# Charge_Board.net
KiCad netlist of a schematic drawn in EAGLE
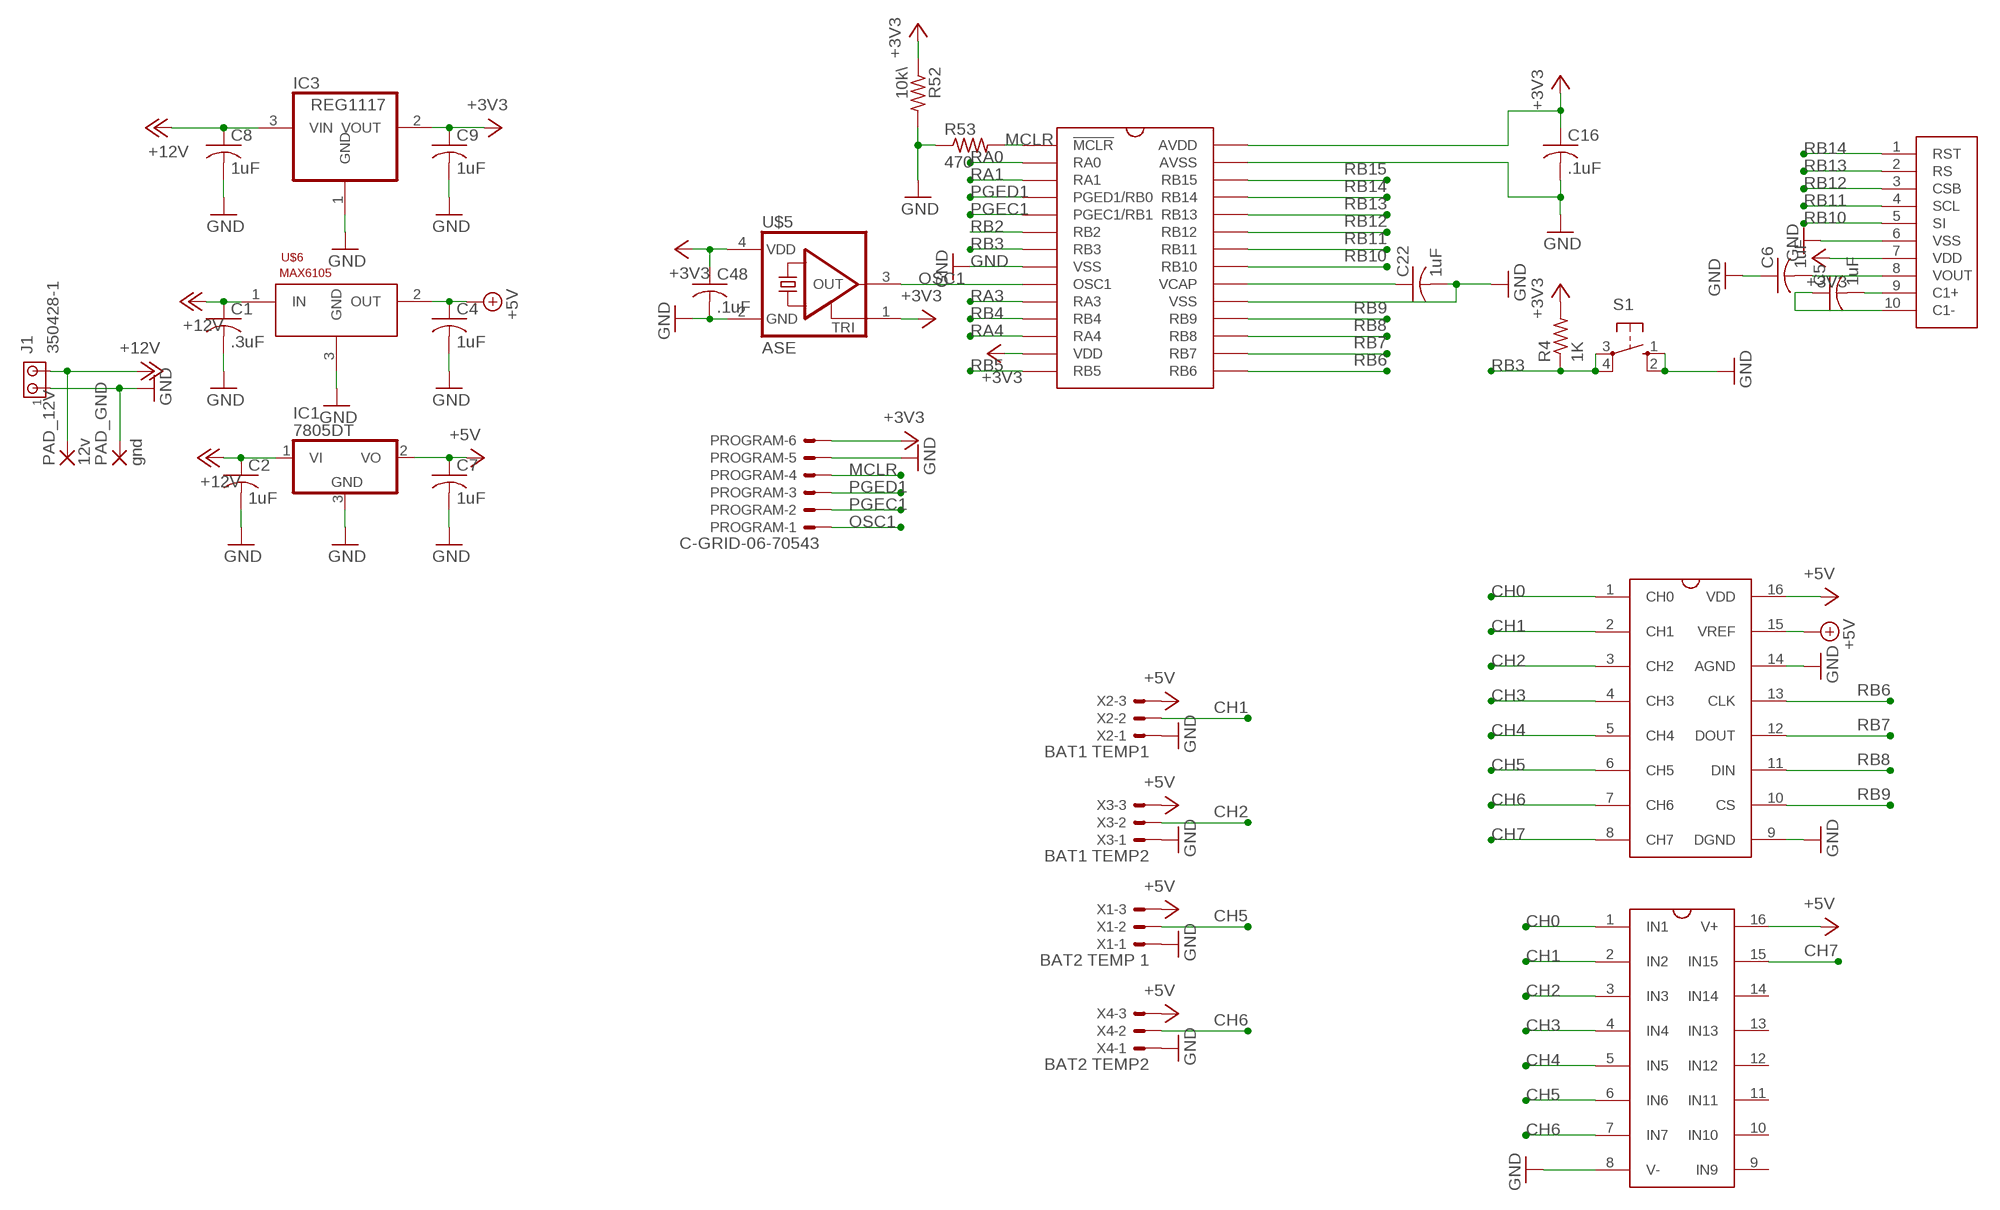
[diagram p0: schematic, sheet 1, part 1 of 2]
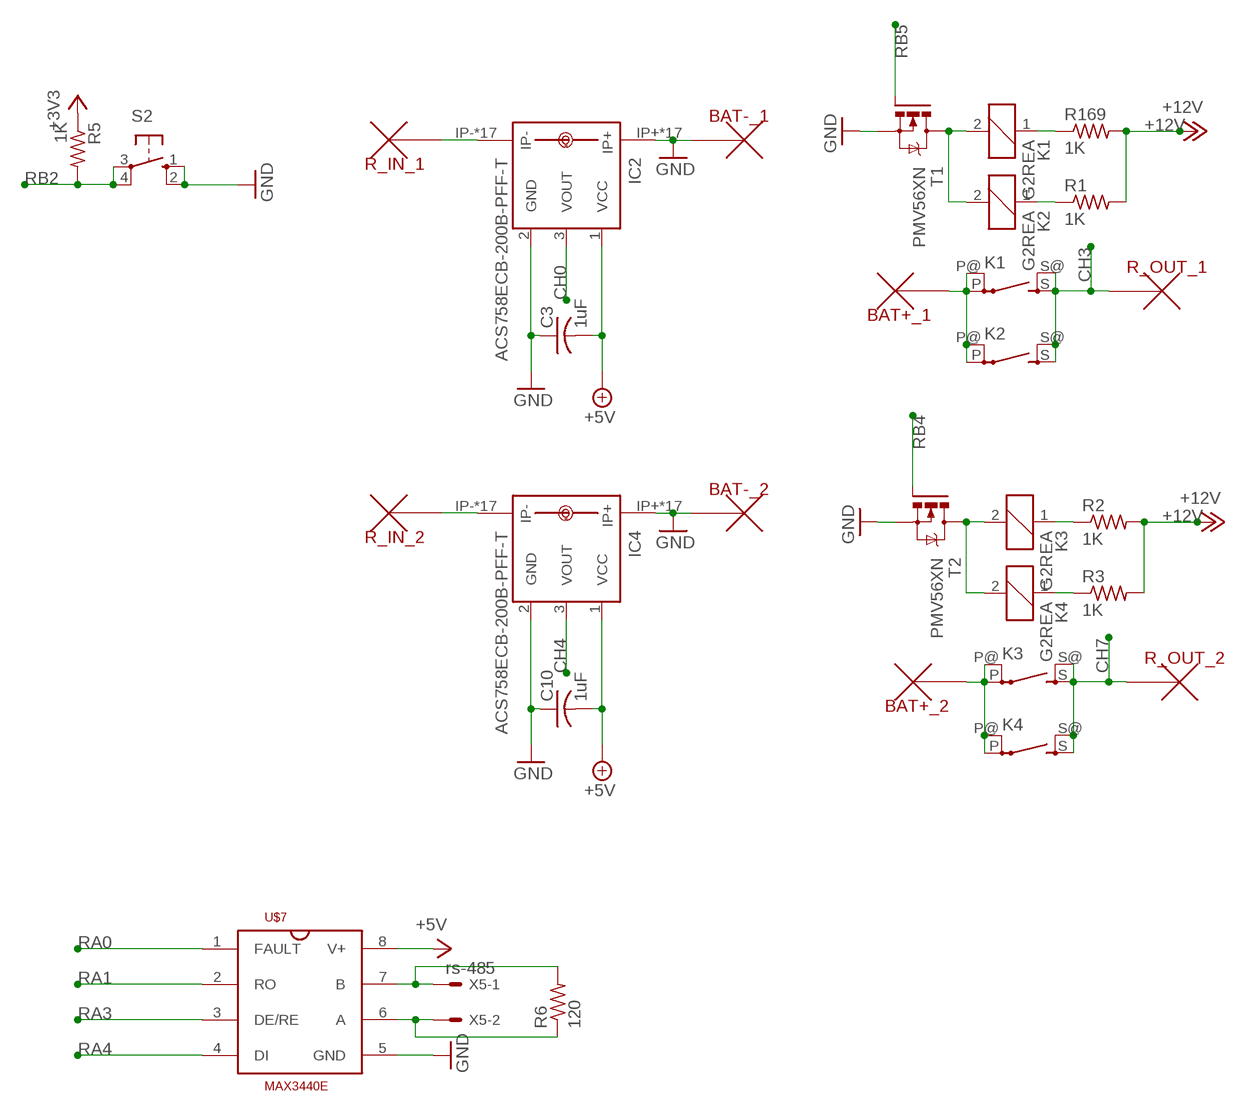
[diagram p1: schematic, sheet 1, part 2 of 2]

(export (version "E")
  (design (tool "Eeschema 10.0.6"))
  (components
    (comp (ref "BAT+_1")
      (value "BAT1 +")
      (footprint "eagle-import:SOLDERPAD")
      (libsource (lib "eagle-import") (part "SOLDERPAD"))
    )
    (comp (ref "BAT+_2")
      (value "BAT2 +")
      (footprint "eagle-import:SOLDERPAD")
      (libsource (lib "eagle-import") (part "SOLDERPAD"))
    )
    (comp (ref "BAT-_1")
      (value "BAT1 GND")
      (footprint "eagle-import:SOLDERPAD")
      (libsource (lib "eagle-import") (part "SOLDERPAD"))
    )
    (comp (ref "BAT-_2")
      (value "BAT2 GND")
      (footprint "eagle-import:SOLDERPAD")
      (libsource (lib "eagle-import") (part "SOLDERPAD"))
    )
    (comp (ref "C1")
      (value ".3uF")
      (footprint "eagle-import:C1206")
      (libsource (lib "eagle-import") (part "C-USC1206"))
    )
    (comp (ref "C2")
      (value "1uF")
      (footprint "eagle-import:C1206")
      (libsource (lib "eagle-import") (part "C-USC1206"))
    )
    (comp (ref "C3")
      (value "1uF")
      (footprint "eagle-import:C1206")
      (libsource (lib "eagle-import") (part "C-USC1206"))
    )
    (comp (ref "C4")
      (value "1uF")
      (footprint "eagle-import:C1206")
      (libsource (lib "eagle-import") (part "C-USC1206"))
    )
    (comp (ref "C5")
      (value "1uF")
      (footprint "eagle-import:C1206")
      (libsource (lib "eagle-import") (part "C-USC1206"))
    )
    (comp (ref "C6")
      (value "1uF")
      (footprint "eagle-import:C1206")
      (libsource (lib "eagle-import") (part "C-USC1206"))
    )
    (comp (ref "C7")
      (value "1uF")
      (footprint "eagle-import:C1206")
      (libsource (lib "eagle-import") (part "C-USC1206"))
    )
    (comp (ref "C8")
      (value "1uF")
      (footprint "eagle-import:C1206")
      (libsource (lib "eagle-import") (part "C-USC1206"))
    )
    (comp (ref "C9")
      (value "1uF")
      (footprint "eagle-import:C1206")
      (libsource (lib "eagle-import") (part "C-USC1206"))
    )
    (comp (ref "C10")
      (value "1uF")
      (footprint "eagle-import:C1206")
      (libsource (lib "eagle-import") (part "C-USC1206"))
    )
    (comp (ref "C16")
      (value ".1uF")
      (footprint "eagle-import:C1206")
      (libsource (lib "eagle-import") (part "C-USC1206"))
    )
    (comp (ref "C22")
      (value "1uF")
      (footprint "eagle-import:C1206")
      (libsource (lib "eagle-import") (part "C-USC1206"))
    )
    (comp (ref "C48")
      (value ".1uF")
      (footprint "eagle-import:C1206")
      (libsource (lib "eagle-import") (part "C-USC1206"))
    )
    (comp (ref "IC1")
      (value "7805DT")
      (footprint "eagle-import:TO252")
      (libsource (lib "eagle-import") (part "78DT05"))
    )
    (comp (ref "IC2")
      (value "ACS758ECB-200B-PFF-T")
      (footprint "eagle-import:CB-PFF")
      (libsource (lib "eagle-import") (part "ACS758ECB-200B-PFF-T"))
    )
    (comp (ref "IC3")
      (value "REG1117")
      (footprint "eagle-import:SOT223")
      (libsource (lib "eagle-import") (part "REG1117"))
    )
    (comp (ref "IC4")
      (value "ACS758ECB-200B-PFF-T")
      (footprint "eagle-import:CB-PFF")
      (libsource (lib "eagle-import") (part "ACS758ECB-200B-PFF-T"))
    )
    (comp (ref "J1")
      (value "350428-1")
      (footprint "eagle-import:350428-1")
      (libsource (lib "eagle-import") (part "350428-1"))
    )
    (comp (ref "K1")
      (value "G2REA")
      (footprint "eagle-import:G2REA")
      (libsource (lib "eagle-import") (part "G2REA"))
    )
    (comp (ref "K2")
      (value "G2REA")
      (footprint "eagle-import:G2REA")
      (libsource (lib "eagle-import") (part "G2REA"))
    )
    (comp (ref "K3")
      (value "G2REA")
      (footprint "eagle-import:G2REA")
      (libsource (lib "eagle-import") (part "G2REA"))
    )
    (comp (ref "K4")
      (value "G2REA")
      (footprint "eagle-import:G2REA")
      (libsource (lib "eagle-import") (part "G2REA"))
    )
    (comp (ref "PAD_12V")
      (value "12v")
      (footprint "eagle-import:3,81_1,4")
      (libsource (lib "eagle-import") (part "3,81/1,4"))
    )
    (comp (ref "PAD_GND")
      (value "gnd")
      (footprint "eagle-import:3,81_1,4")
      (libsource (lib "eagle-import") (part "3,81/1,4"))
    )
    (comp (ref "PROGRAM")
      (value "C-GRID-06-70543")
      (footprint "eagle-import:70543-06")
      (libsource (lib "eagle-import") (part "C-GRID-06-70543"))
    )
    (comp (ref "R1")
      (value "1K")
      (footprint "eagle-import:R1206")
      (libsource (lib "eagle-import") (part "R-US_R1206"))
    )
    (comp (ref "R2")
      (value "1K")
      (footprint "eagle-import:R1206")
      (libsource (lib "eagle-import") (part "R-US_R1206"))
    )
    (comp (ref "R3")
      (value "1K")
      (footprint "eagle-import:R1206")
      (libsource (lib "eagle-import") (part "R-US_R1206"))
    )
    (comp (ref "R4")
      (value "1K")
      (footprint "eagle-import:R1206")
      (libsource (lib "eagle-import") (part "R-US_R1206"))
    )
    (comp (ref "R5")
      (value "1K")
      (footprint "eagle-import:R1206")
      (libsource (lib "eagle-import") (part "R-US_R1206"))
    )
    (comp (ref "R6")
      (value "120")
      (footprint "eagle-import:R1206")
      (libsource (lib "eagle-import") (part "R-US_R1206"))
    )
    (comp (ref "R52")
      (value "10k\\")
      (footprint "eagle-import:R1206")
      (libsource (lib "eagle-import") (part "R-US_R1206"))
    )
    (comp (ref "R53")
      (value "470")
      (footprint "eagle-import:R1206")
      (libsource (lib "eagle-import") (part "R-US_R1206"))
    )
    (comp (ref "R169")
      (value "1K")
      (footprint "eagle-import:R1206")
      (libsource (lib "eagle-import") (part "R-US_R1206"))
    )
    (comp (ref "R_IN_1")
      (value "R1 IN")
      (footprint "eagle-import:SOLDERPAD")
      (libsource (lib "eagle-import") (part "SOLDERPAD"))
    )
    (comp (ref "R_IN_2")
      (value "R2 IN")
      (footprint "eagle-import:SOLDERPAD")
      (libsource (lib "eagle-import") (part "SOLDERPAD"))
    )
    (comp (ref "R_OUT_1")
      (value "R1 OUT")
      (footprint "eagle-import:SOLDERPAD")
      (libsource (lib "eagle-import") (part "SOLDERPAD"))
    )
    (comp (ref "R_OUT_2")
      (value "R2 OUT")
      (footprint "eagle-import:SOLDERPAD")
      (libsource (lib "eagle-import") (part "SOLDERPAD"))
    )
    (comp (ref "S1")
      (value "10-XX")
      (footprint "eagle-import:B3F-10XX")
      (fields (field (name "MPN") "B3F-1000"))
      (libsource (lib "eagle-import") (part "10-XX"))
    )
    (comp (ref "S2")
      (value "10-XX")
      (footprint "eagle-import:B3F-10XX")
      (fields (field (name "MPN") "B3F-1000"))
      (libsource (lib "eagle-import") (part "10-XX"))
    )
    (comp (ref "T1")
      (value "PMV56XN")
      (footprint "eagle-import:SOT23")
      (fields (field (name "PART_NUM") "PMV56XN,215"))
      (libsource (lib "eagle-import") (part "N-CHANNEL_MOSFETPMV56XN,215"))
    )
    (comp (ref "T2")
      (value "PMV56XN")
      (footprint "eagle-import:SOT23")
      (fields (field (name "PART_NUM") "PMV56XN,215"))
      (libsource (lib "eagle-import") (part "N-CHANNEL_MOSFETPMV56XN,215"))
    )
    (comp (ref "U$1")
      (value "MCP-3008")
      (footprint "eagle-import:SO16")
      (libsource (lib "eagle-import") (part "MCP-3008"))
    )
    (comp (ref "U$2")
      (value "LCD_SCREEN")
      (footprint "eagle-import:LCD_SCREEN")
      (libsource (lib "eagle-import") (part "LCD_SCREEN"))
    )
    (comp (ref "U$3")
      (value "SP720APP")
      (footprint "eagle-import:SO16")
      (libsource (lib "eagle-import") (part "SP720APP"))
    )
    (comp (ref "U$4")
      (value "PIC24HJ128GP-202")
      (footprint "eagle-import:SO28W")
      (libsource (lib "eagle-import") (part "PIC24HJ128GP-202"))
    )
    (comp (ref "U$5")
      (value "ASE")
      (footprint "eagle-import:ASE")
      (libsource (lib "eagle-import") (part "ASE"))
    )
    (comp (ref "U$6")
      (value "MAX6105")
      (footprint "eagle-import:SOT23")
      (libsource (lib "eagle-import") (part "MAX6103"))
    )
    (comp (ref "U$7")
      (value "MAX3440E")
      (footprint "eagle-import:SO-08")
      (libsource (lib "eagle-import") (part "MAX3440E"))
    )
    (comp (ref "X1")
      (value "BAT2 TEMP 1")
      (footprint "eagle-import:70543-03")
      (libsource (lib "eagle-import") (part "C-GRID-03-70543"))
    )
    (comp (ref "X2")
      (value "BAT1 TEMP1")
      (footprint "eagle-import:70543-03")
      (libsource (lib "eagle-import") (part "C-GRID-03-70543"))
    )
    (comp (ref "X3")
      (value "BAT1 TEMP2")
      (footprint "eagle-import:70543-03")
      (libsource (lib "eagle-import") (part "C-GRID-03-70543"))
    )
    (comp (ref "X4")
      (value "BAT2 TEMP2")
      (footprint "eagle-import:70543-03")
      (libsource (lib "eagle-import") (part "C-GRID-03-70543"))
    )
    (comp (ref "X5")
      (value "rs-485")
      (footprint "eagle-import:70543-02")
      (libsource (lib "eagle-import") (part "C-GRID-02-70543"))
    )
  )
  (nets
    (net (code "1") (name "+3V3") (class "Default")
      (node (ref "C16") (pin "1") (pinfunction "1_1") (pintype "passive"))
      (node (ref "C48") (pin "1") (pinfunction "1_1") (pintype "passive"))
      (node (ref "C9") (pin "1") (pinfunction "1_1") (pintype "passive"))
      (node (ref "IC3") (pin "2") (pinfunction "VOUT_2") (pintype "output"))
      (node (ref "PROGRAM") (pin "6") (pinfunction "S_6") (pintype "passive"))
      (node (ref "R4") (pin "2") (pinfunction "2_2") (pintype "passive"))
      (node (ref "R5") (pin "1") (pinfunction "1_1") (pintype "passive"))
      (node (ref "R52") (pin "1") (pinfunction "1_1") (pintype "passive"))
      (node (ref "U$2") (pin "7") (pinfunction "VDD_7") (pintype "bidirectional"))
      (node (ref "U$4") (pin "13") (pinfunction "VDD_13") (pintype "bidirectional"))
      (node (ref "U$4") (pin "28") (pinfunction "AVDD_28") (pintype "bidirectional"))
      (node (ref "U$5") (pin "1") (pinfunction "TRI_1") (pintype "input"))
      (node (ref "U$5") (pin "4") (pinfunction "VDD_4") (pintype "power_in"))
    )
    (net (code "2") (name "+5V") (class "Default")
      (node (ref "C10") (pin "2") (pinfunction "2_2") (pintype "passive"))
      (node (ref "C3") (pin "2") (pinfunction "2_2") (pintype "passive"))
      (node (ref "C4") (pin "1") (pinfunction "1_1") (pintype "passive"))
      (node (ref "C7") (pin "1") (pinfunction "1_1") (pintype "passive"))
      (node (ref "IC1") (pin "2") (pinfunction "VO_2") (pintype "passive"))
      (node (ref "IC2") (pin "1") (pinfunction "VCC_1") (pintype "power_in"))
      (node (ref "IC4") (pin "1") (pinfunction "VCC_1") (pintype "power_in"))
      (node (ref "U$1") (pin "15") (pinfunction "VREF_15") (pintype "bidirectional"))
      (node (ref "U$1") (pin "16") (pinfunction "VDD_16") (pintype "bidirectional"))
      (node (ref "U$3") (pin "16") (pinfunction "V+_16") (pintype "bidirectional"))
      (node (ref "U$6") (pin "2") (pinfunction "OUT_2") (pintype "bidirectional"))
      (node (ref "U$7") (pin "8") (pinfunction "V+_8") (pintype "bidirectional"))
      (node (ref "X1") (pin "3") (pinfunction "S_3") (pintype "passive"))
      (node (ref "X2") (pin "3") (pinfunction "S_3") (pintype "passive"))
      (node (ref "X3") (pin "3") (pinfunction "S_3") (pintype "passive"))
      (node (ref "X4") (pin "3") (pinfunction "S_3") (pintype "passive"))
    )
    (net (code "3") (name "+12V") (class "Default")
      (node (ref "C1") (pin "1") (pinfunction "1_1") (pintype "passive"))
      (node (ref "C2") (pin "1") (pinfunction "1_1") (pintype "passive"))
      (node (ref "C8") (pin "1") (pinfunction "1_1") (pintype "passive"))
      (node (ref "IC1") (pin "1") (pinfunction "VI_1") (pintype "input"))
      (node (ref "IC3") (pin "3") (pinfunction "VIN_3") (pintype "input"))
      (node (ref "J1") (pin "2") (pinfunction "2_2") (pintype "passive"))
      (node (ref "PAD_12V") (pin "1") (pinfunction "P_1") (pintype "passive"))
      (node (ref "R1") (pin "2") (pinfunction "2_2") (pintype "passive"))
      (node (ref "R169") (pin "2") (pinfunction "2_2") (pintype "passive"))
      (node (ref "R2") (pin "2") (pinfunction "2_2") (pintype "passive"))
      (node (ref "R3") (pin "2") (pinfunction "2_2") (pintype "passive"))
      (node (ref "U$6") (pin "1") (pinfunction "IN_1") (pintype "bidirectional"))
    )
    (net (code "4") (name "/CH0") (class "Default")
      (node (ref "IC2") (pin "3") (pinfunction "VOUT_3") (pintype "output"))
      (node (ref "U$1") (pin "1") (pinfunction "CH0_1") (pintype "bidirectional"))
      (node (ref "U$3") (pin "1") (pinfunction "IN1_1") (pintype "bidirectional"))
    )
    (net (code "5") (name "/CH1") (class "Default")
      (node (ref "U$1") (pin "2") (pinfunction "CH1_2") (pintype "bidirectional"))
      (node (ref "U$3") (pin "2") (pinfunction "IN2_2") (pintype "bidirectional"))
      (node (ref "X2") (pin "2") (pinfunction "S_2") (pintype "passive"))
    )
    (net (code "6") (name "/CH2") (class "Default")
      (node (ref "U$1") (pin "3") (pinfunction "CH2_3") (pintype "bidirectional"))
      (node (ref "U$3") (pin "3") (pinfunction "IN3_3") (pintype "bidirectional"))
      (node (ref "X3") (pin "2") (pinfunction "S_2") (pintype "passive"))
    )
    (net (code "7") (name "/CH3") (class "Default")
      (node (ref "K1") (pin "S") (pinfunction "S_S") (pintype "passive"))
      (node (ref "K1") (pin "S@") (pinfunction "S_S@") (pintype "passive"))
      (node (ref "K2") (pin "S") (pinfunction "S_S") (pintype "passive"))
      (node (ref "K2") (pin "S@") (pinfunction "S_S@") (pintype "passive"))
      (node (ref "R_OUT_1") (pin "P$1") (pinfunction "P$1_P$1") (pintype "bidirectional"))
      (node (ref "U$1") (pin "4") (pinfunction "CH3_4") (pintype "bidirectional"))
      (node (ref "U$3") (pin "4") (pinfunction "IN4_4") (pintype "bidirectional"))
    )
    (net (code "8") (name "/CH4") (class "Default")
      (node (ref "IC4") (pin "3") (pinfunction "VOUT_3") (pintype "output"))
      (node (ref "U$1") (pin "5") (pinfunction "CH4_5") (pintype "bidirectional"))
      (node (ref "U$3") (pin "5") (pinfunction "IN5_5") (pintype "bidirectional"))
    )
    (net (code "9") (name "/CH5") (class "Default")
      (node (ref "U$1") (pin "6") (pinfunction "CH5_6") (pintype "bidirectional"))
      (node (ref "U$3") (pin "6") (pinfunction "IN6_6") (pintype "bidirectional"))
      (node (ref "X1") (pin "2") (pinfunction "S_2") (pintype "passive"))
    )
    (net (code "10") (name "/CH6") (class "Default")
      (node (ref "U$1") (pin "7") (pinfunction "CH6_7") (pintype "bidirectional"))
      (node (ref "U$3") (pin "7") (pinfunction "IN7_7") (pintype "bidirectional"))
      (node (ref "X4") (pin "2") (pinfunction "S_2") (pintype "passive"))
    )
    (net (code "11") (name "/CH7") (class "Default")
      (node (ref "K3") (pin "S") (pinfunction "S_S") (pintype "passive"))
      (node (ref "K3") (pin "S@") (pinfunction "S_S@") (pintype "passive"))
      (node (ref "K4") (pin "S") (pinfunction "S_S") (pintype "passive"))
      (node (ref "K4") (pin "S@") (pinfunction "S_S@") (pintype "passive"))
      (node (ref "R_OUT_2") (pin "P$1") (pinfunction "P$1_P$1") (pintype "bidirectional"))
      (node (ref "U$1") (pin "8") (pinfunction "CH7_8") (pintype "bidirectional"))
      (node (ref "U$3") (pin "15") (pinfunction "IN15_15") (pintype "bidirectional"))
    )
    (net (code "12") (name "/MCLR") (class "Default")
      (node (ref "PROGRAM") (pin "4") (pinfunction "S_4") (pintype "passive"))
      (node (ref "R53") (pin "2") (pinfunction "2_2") (pintype "passive"))
      (node (ref "U$4") (pin "1") (pinfunction "~{MCLR}_1") (pintype "bidirectional"))
    )
    (net (code "13") (name "/OSC1") (class "Default")
      (node (ref "PROGRAM") (pin "1") (pinfunction "S_1") (pintype "passive"))
      (node (ref "U$4") (pin "9") (pinfunction "OSC1_9") (pintype "bidirectional"))
      (node (ref "U$5") (pin "3") (pinfunction "OUT_3") (pintype "output"))
    )
    (net (code "14") (name "/PGEC1") (class "Default")
      (node (ref "PROGRAM") (pin "2") (pinfunction "S_2") (pintype "passive"))
      (node (ref "U$4") (pin "5") (pinfunction "PGEC1/RB1_5") (pintype "bidirectional"))
    )
    (net (code "15") (name "/PGED1") (class "Default")
      (node (ref "PROGRAM") (pin "3") (pinfunction "S_3") (pintype "passive"))
      (node (ref "U$4") (pin "4") (pinfunction "PGED1/RB0_4") (pintype "bidirectional"))
    )
    (net (code "16") (name "/RA0") (class "Default")
      (node (ref "U$4") (pin "2") (pinfunction "RA0_2") (pintype "bidirectional"))
      (node (ref "U$7") (pin "1") (pinfunction "FAULT_1") (pintype "bidirectional"))
    )
    (net (code "17") (name "/RA1") (class "Default")
      (node (ref "U$4") (pin "3") (pinfunction "RA1_3") (pintype "bidirectional"))
      (node (ref "U$7") (pin "2") (pinfunction "RO_2") (pintype "bidirectional"))
    )
    (net (code "18") (name "/RA3") (class "Default")
      (node (ref "U$4") (pin "10") (pinfunction "RA3_10") (pintype "bidirectional"))
      (node (ref "U$7") (pin "3") (pinfunction "DE/RE_3") (pintype "bidirectional"))
    )
    (net (code "19") (name "/RA4") (class "Default")
      (node (ref "U$4") (pin "12") (pinfunction "RA4_12") (pintype "bidirectional"))
      (node (ref "U$7") (pin "4") (pinfunction "DI_4") (pintype "bidirectional"))
    )
    (net (code "20") (name "/RB2") (class "Default")
      (node (ref "R5") (pin "2") (pinfunction "2_2") (pintype "passive"))
      (node (ref "S2") (pin "3") (pinfunction "P_3") (pintype "passive"))
      (node (ref "S2") (pin "4") (pinfunction "P1_4") (pintype "passive"))
      (node (ref "U$4") (pin "6") (pinfunction "RB2_6") (pintype "bidirectional"))
    )
    (net (code "21") (name "/RB3") (class "Default")
      (node (ref "R4") (pin "1") (pinfunction "1_1") (pintype "passive"))
      (node (ref "S1") (pin "3") (pinfunction "P_3") (pintype "passive"))
      (node (ref "S1") (pin "4") (pinfunction "P1_4") (pintype "passive"))
      (node (ref "U$4") (pin "7") (pinfunction "RB3_7") (pintype "bidirectional"))
    )
    (net (code "22") (name "/RB4") (class "Default")
      (node (ref "T2") (pin "1") (pinfunction "G_1") (pintype "passive"))
      (node (ref "U$4") (pin "11") (pinfunction "RB4_11") (pintype "bidirectional"))
    )
    (net (code "23") (name "/RB5") (class "Default")
      (node (ref "T1") (pin "1") (pinfunction "G_1") (pintype "passive"))
      (node (ref "U$4") (pin "14") (pinfunction "RB5_14") (pintype "bidirectional"))
    )
    (net (code "24") (name "/RB6") (class "Default")
      (node (ref "U$1") (pin "13") (pinfunction "CLK_13") (pintype "bidirectional"))
      (node (ref "U$4") (pin "15") (pinfunction "RB6_15") (pintype "bidirectional"))
    )
    (net (code "25") (name "/RB7") (class "Default")
      (node (ref "U$1") (pin "12") (pinfunction "DOUT_12") (pintype "bidirectional"))
      (node (ref "U$4") (pin "16") (pinfunction "RB7_16") (pintype "bidirectional"))
    )
    (net (code "26") (name "/RB8") (class "Default")
      (node (ref "U$1") (pin "11") (pinfunction "DIN_11") (pintype "bidirectional"))
      (node (ref "U$4") (pin "17") (pinfunction "RB8_17") (pintype "bidirectional"))
    )
    (net (code "27") (name "/RB9") (class "Default")
      (node (ref "U$1") (pin "10") (pinfunction "CS_10") (pintype "bidirectional"))
      (node (ref "U$4") (pin "18") (pinfunction "RB9_18") (pintype "bidirectional"))
    )
    (net (code "28") (name "/RB10") (class "Default")
      (node (ref "U$2") (pin "5") (pinfunction "SI_5") (pintype "bidirectional"))
      (node (ref "U$4") (pin "21") (pinfunction "RB10_21") (pintype "bidirectional"))
    )
    (net (code "29") (name "/RB11") (class "Default")
      (node (ref "U$2") (pin "4") (pinfunction "SCL_4") (pintype "bidirectional"))
      (node (ref "U$4") (pin "22") (pinfunction "RB11_22") (pintype "bidirectional"))
    )
    (net (code "30") (name "/RB12") (class "Default")
      (node (ref "U$2") (pin "3") (pinfunction "CSB_3") (pintype "bidirectional"))
      (node (ref "U$4") (pin "23") (pinfunction "RB12_23") (pintype "bidirectional"))
    )
    (net (code "31") (name "/RB13") (class "Default")
      (node (ref "U$2") (pin "2") (pinfunction "RS_2") (pintype "bidirectional"))
      (node (ref "U$4") (pin "24") (pinfunction "RB13_24") (pintype "bidirectional"))
    )
    (net (code "32") (name "/RB14") (class "Default")
      (node (ref "U$2") (pin "1") (pinfunction "RST_1") (pintype "bidirectional"))
      (node (ref "U$4") (pin "25") (pinfunction "RB14_25") (pintype "bidirectional"))
    )
    (net (code "33") (name "/RB15") (class "Default")
      (node (ref "U$4") (pin "26") (pinfunction "RB15_26") (pintype "bidirectional"))
    )
    (net (code "34") (name "GND") (class "Default")
      (node (ref "BAT-_1") (pin "P$1") (pinfunction "P$1_P$1") (pintype "bidirectional"))
      (node (ref "BAT-_2") (pin "P$1") (pinfunction "P$1_P$1") (pintype "bidirectional"))
      (node (ref "C1") (pin "2") (pinfunction "2_2") (pintype "passive"))
      (node (ref "C10") (pin "1") (pinfunction "1_1") (pintype "passive"))
      (node (ref "C16") (pin "2") (pinfunction "2_2") (pintype "passive"))
      (node (ref "C2") (pin "2") (pinfunction "2_2") (pintype "passive"))
      (node (ref "C22") (pin "2") (pinfunction "2_2") (pintype "passive"))
      (node (ref "C3") (pin "1") (pinfunction "1_1") (pintype "passive"))
      (node (ref "C4") (pin "2") (pinfunction "2_2") (pintype "passive"))
      (node (ref "C48") (pin "2") (pinfunction "2_2") (pintype "passive"))
      (node (ref "C6") (pin "1") (pinfunction "1_1") (pintype "passive"))
      (node (ref "C7") (pin "2") (pinfunction "2_2") (pintype "passive"))
      (node (ref "C8") (pin "2") (pinfunction "2_2") (pintype "passive"))
      (node (ref "C9") (pin "2") (pinfunction "2_2") (pintype "passive"))
      (node (ref "IC1") (pin "3") (pinfunction "GND_3") (pintype "passive"))
      (node (ref "IC2") (pin "2") (pinfunction "GND_2") (pintype "power_in"))
      (node (ref "IC2") (pin "IP+") (pinfunction "IP+_IP+") (pintype "passive"))
      (node (ref "IC2") (pin "IP+@10") (pinfunction "IP+_IP+@10") (pintype "passive"))
      (node (ref "IC2") (pin "IP+@11") (pinfunction "IP+_IP+@11") (pintype "passive"))
      (node (ref "IC2") (pin "IP+@12") (pinfunction "IP+_IP+@12") (pintype "passive"))
      (node (ref "IC2") (pin "IP+@13") (pinfunction "IP+_IP+@13") (pintype "passive"))
      (node (ref "IC2") (pin "IP+@14") (pinfunction "IP+_IP+@14") (pintype "passive"))
      (node (ref "IC2") (pin "IP+@15") (pinfunction "IP+_IP+@15") (pintype "passive"))
      (node (ref "IC2") (pin "IP+@16") (pinfunction "IP+_IP+@16") (pintype "passive"))
      (node (ref "IC2") (pin "IP+@17") (pinfunction "IP+_IP+@17") (pintype "passive"))
      (node (ref "IC2") (pin "IP+@2") (pinfunction "IP+_IP+@2") (pintype "passive"))
      (node (ref "IC2") (pin "IP+@3") (pinfunction "IP+_IP+@3") (pintype "passive"))
      (node (ref "IC2") (pin "IP+@4") (pinfunction "IP+_IP+@4") (pintype "passive"))
      (node (ref "IC2") (pin "IP+@5") (pinfunction "IP+_IP+@5") (pintype "passive"))
      (node (ref "IC2") (pin "IP+@6") (pinfunction "IP+_IP+@6") (pintype "passive"))
      (node (ref "IC2") (pin "IP+@7") (pinfunction "IP+_IP+@7") (pintype "passive"))
      (node (ref "IC2") (pin "IP+@8") (pinfunction "IP+_IP+@8") (pintype "passive"))
      (node (ref "IC2") (pin "IP+@9") (pinfunction "IP+_IP+@9") (pintype "passive"))
      (node (ref "IC3") (pin "1") (pinfunction "GND_1") (pintype "power_in"))
      (node (ref "IC4") (pin "2") (pinfunction "GND_2") (pintype "power_in"))
      (node (ref "IC4") (pin "IP+") (pinfunction "IP+_IP+") (pintype "passive"))
      (node (ref "IC4") (pin "IP+@10") (pinfunction "IP+_IP+@10") (pintype "passive"))
      (node (ref "IC4") (pin "IP+@11") (pinfunction "IP+_IP+@11") (pintype "passive"))
      (node (ref "IC4") (pin "IP+@12") (pinfunction "IP+_IP+@12") (pintype "passive"))
      (node (ref "IC4") (pin "IP+@13") (pinfunction "IP+_IP+@13") (pintype "passive"))
      (node (ref "IC4") (pin "IP+@14") (pinfunction "IP+_IP+@14") (pintype "passive"))
      (node (ref "IC4") (pin "IP+@15") (pinfunction "IP+_IP+@15") (pintype "passive"))
      (node (ref "IC4") (pin "IP+@16") (pinfunction "IP+_IP+@16") (pintype "passive"))
      (node (ref "IC4") (pin "IP+@17") (pinfunction "IP+_IP+@17") (pintype "passive"))
      (node (ref "IC4") (pin "IP+@2") (pinfunction "IP+_IP+@2") (pintype "passive"))
      (node (ref "IC4") (pin "IP+@3") (pinfunction "IP+_IP+@3") (pintype "passive"))
      (node (ref "IC4") (pin "IP+@4") (pinfunction "IP+_IP+@4") (pintype "passive"))
      (node (ref "IC4") (pin "IP+@5") (pinfunction "IP+_IP+@5") (pintype "passive"))
      (node (ref "IC4") (pin "IP+@6") (pinfunction "IP+_IP+@6") (pintype "passive"))
      (node (ref "IC4") (pin "IP+@7") (pinfunction "IP+_IP+@7") (pintype "passive"))
      (node (ref "IC4") (pin "IP+@8") (pinfunction "IP+_IP+@8") (pintype "passive"))
      (node (ref "IC4") (pin "IP+@9") (pinfunction "IP+_IP+@9") (pintype "passive"))
      (node (ref "J1") (pin "1") (pinfunction "1_1") (pintype "passive"))
      (node (ref "PAD_GND") (pin "1") (pinfunction "P_1") (pintype "passive"))
      (node (ref "PROGRAM") (pin "5") (pinfunction "S_5") (pintype "passive"))
      (node (ref "R52") (pin "2") (pinfunction "2_2") (pintype "passive"))
      (node (ref "R53") (pin "1") (pinfunction "1_1") (pintype "passive"))
      (node (ref "S1") (pin "1") (pinfunction "S_1") (pintype "passive"))
      (node (ref "S1") (pin "2") (pinfunction "S1_2") (pintype "passive"))
      (node (ref "S2") (pin "1") (pinfunction "S_1") (pintype "passive"))
      (node (ref "S2") (pin "2") (pinfunction "S1_2") (pintype "passive"))
      (node (ref "T1") (pin "2") (pinfunction "S_2") (pintype "passive"))
      (node (ref "T2") (pin "2") (pinfunction "S_2") (pintype "passive"))
      (node (ref "U$1") (pin "14") (pinfunction "AGND_14") (pintype "bidirectional"))
      (node (ref "U$1") (pin "9") (pinfunction "DGND_9") (pintype "bidirectional"))
      (node (ref "U$2") (pin "6") (pinfunction "VSS_6") (pintype "bidirectional"))
      (node (ref "U$3") (pin "8") (pinfunction "V-_8") (pintype "bidirectional"))
      (node (ref "U$4") (pin "19") (pinfunction "VSS_19") (pintype "bidirectional"))
      (node (ref "U$4") (pin "27") (pinfunction "AVSS_27") (pintype "bidirectional"))
      (node (ref "U$4") (pin "8") (pinfunction "VSS_8") (pintype "bidirectional"))
      (node (ref "U$5") (pin "2") (pinfunction "GND_2") (pintype "power_in"))
      (node (ref "U$6") (pin "3") (pinfunction "GND_3") (pintype "bidirectional"))
      (node (ref "U$7") (pin "5") (pinfunction "GND_5") (pintype "bidirectional"))
      (node (ref "X1") (pin "1") (pinfunction "S_1") (pintype "passive"))
      (node (ref "X2") (pin "1") (pinfunction "S_1") (pintype "passive"))
      (node (ref "X3") (pin "1") (pinfunction "S_1") (pintype "passive"))
      (node (ref "X4") (pin "1") (pinfunction "S_1") (pintype "passive"))
    )
    (net (code "35") (name "Net-(BAT+_1-PadP$1)") (class "Default")
      (node (ref "BAT+_1") (pin "P$1") (pinfunction "P$1_P$1") (pintype "bidirectional"))
      (node (ref "K1") (pin "P") (pinfunction "P_P") (pintype "passive"))
      (node (ref "K1") (pin "P@") (pinfunction "P_P@") (pintype "passive"))
      (node (ref "K2") (pin "P") (pinfunction "P_P") (pintype "passive"))
      (node (ref "K2") (pin "P@") (pinfunction "P_P@") (pintype "passive"))
    )
    (net (code "36") (name "Net-(BAT+_2-PadP$1)") (class "Default")
      (node (ref "BAT+_2") (pin "P$1") (pinfunction "P$1_P$1") (pintype "bidirectional"))
      (node (ref "K3") (pin "P") (pinfunction "P_P") (pintype "passive"))
      (node (ref "K3") (pin "P@") (pinfunction "P_P@") (pintype "passive"))
      (node (ref "K4") (pin "P") (pinfunction "P_P") (pintype "passive"))
      (node (ref "K4") (pin "P@") (pinfunction "P_P@") (pintype "passive"))
    )
    (net (code "37") (name "Net-(IC2-IP--PadIP-@10)") (class "Default")
      (node (ref "IC2") (pin "IP-") (pinfunction "IP-_IP-") (pintype "passive"))
      (node (ref "IC2") (pin "IP-@10") (pinfunction "IP-_IP-@10") (pintype "passive"))
      (node (ref "IC2") (pin "IP-@11") (pinfunction "IP-_IP-@11") (pintype "passive"))
      (node (ref "IC2") (pin "IP-@12") (pinfunction "IP-_IP-@12") (pintype "passive"))
      (node (ref "IC2") (pin "IP-@13") (pinfunction "IP-_IP-@13") (pintype "passive"))
      (node (ref "IC2") (pin "IP-@14") (pinfunction "IP-_IP-@14") (pintype "passive"))
      (node (ref "IC2") (pin "IP-@15") (pinfunction "IP-_IP-@15") (pintype "passive"))
      (node (ref "IC2") (pin "IP-@16") (pinfunction "IP-_IP-@16") (pintype "passive"))
      (node (ref "IC2") (pin "IP-@17") (pinfunction "IP-_IP-@17") (pintype "passive"))
      (node (ref "IC2") (pin "IP-@2") (pinfunction "IP-_IP-@2") (pintype "passive"))
      (node (ref "IC2") (pin "IP-@3") (pinfunction "IP-_IP-@3") (pintype "passive"))
      (node (ref "IC2") (pin "IP-@4") (pinfunction "IP-_IP-@4") (pintype "passive"))
      (node (ref "IC2") (pin "IP-@5") (pinfunction "IP-_IP-@5") (pintype "passive"))
      (node (ref "IC2") (pin "IP-@6") (pinfunction "IP-_IP-@6") (pintype "passive"))
      (node (ref "IC2") (pin "IP-@7") (pinfunction "IP-_IP-@7") (pintype "passive"))
      (node (ref "IC2") (pin "IP-@8") (pinfunction "IP-_IP-@8") (pintype "passive"))
      (node (ref "IC2") (pin "IP-@9") (pinfunction "IP-_IP-@9") (pintype "passive"))
      (node (ref "R_IN_1") (pin "P$1") (pinfunction "P$1_P$1") (pintype "bidirectional"))
    )
    (net (code "38") (name "Net-(IC4-IP--PadIP-@10)") (class "Default")
      (node (ref "IC4") (pin "IP-") (pinfunction "IP-_IP-") (pintype "passive"))
      (node (ref "IC4") (pin "IP-@10") (pinfunction "IP-_IP-@10") (pintype "passive"))
      (node (ref "IC4") (pin "IP-@11") (pinfunction "IP-_IP-@11") (pintype "passive"))
      (node (ref "IC4") (pin "IP-@12") (pinfunction "IP-_IP-@12") (pintype "passive"))
      (node (ref "IC4") (pin "IP-@13") (pinfunction "IP-_IP-@13") (pintype "passive"))
      (node (ref "IC4") (pin "IP-@14") (pinfunction "IP-_IP-@14") (pintype "passive"))
      (node (ref "IC4") (pin "IP-@15") (pinfunction "IP-_IP-@15") (pintype "passive"))
      (node (ref "IC4") (pin "IP-@16") (pinfunction "IP-_IP-@16") (pintype "passive"))
      (node (ref "IC4") (pin "IP-@17") (pinfunction "IP-_IP-@17") (pintype "passive"))
      (node (ref "IC4") (pin "IP-@2") (pinfunction "IP-_IP-@2") (pintype "passive"))
      (node (ref "IC4") (pin "IP-@3") (pinfunction "IP-_IP-@3") (pintype "passive"))
      (node (ref "IC4") (pin "IP-@4") (pinfunction "IP-_IP-@4") (pintype "passive"))
      (node (ref "IC4") (pin "IP-@5") (pinfunction "IP-_IP-@5") (pintype "passive"))
      (node (ref "IC4") (pin "IP-@6") (pinfunction "IP-_IP-@6") (pintype "passive"))
      (node (ref "IC4") (pin "IP-@7") (pinfunction "IP-_IP-@7") (pintype "passive"))
      (node (ref "IC4") (pin "IP-@8") (pinfunction "IP-_IP-@8") (pintype "passive"))
      (node (ref "IC4") (pin "IP-@9") (pinfunction "IP-_IP-@9") (pintype "passive"))
      (node (ref "R_IN_2") (pin "P$1") (pinfunction "P$1_P$1") (pintype "bidirectional"))
    )
    (net (code "39") (name "Net-(K1-Pad1)") (class "Default")
      (node (ref "K1") (pin "1") (pinfunction "1_1") (pintype "passive"))
      (node (ref "R169") (pin "1") (pinfunction "1_1") (pintype "passive"))
    )
    (net (code "40") (name "Net-(K2-Pad1)") (class "Default")
      (node (ref "K2") (pin "1") (pinfunction "1_1") (pintype "passive"))
      (node (ref "R1") (pin "1") (pinfunction "1_1") (pintype "passive"))
    )
    (net (code "41") (name "Net-(K3-Pad1)") (class "Default")
      (node (ref "K3") (pin "1") (pinfunction "1_1") (pintype "passive"))
      (node (ref "R2") (pin "1") (pinfunction "1_1") (pintype "passive"))
    )
    (net (code "42") (name "Net-(K4-Pad1)") (class "Default")
      (node (ref "K4") (pin "1") (pinfunction "1_1") (pintype "passive"))
      (node (ref "R3") (pin "1") (pinfunction "1_1") (pintype "passive"))
    )
    (net (code "43") (name "Net-(T1-D)") (class "Default")
      (node (ref "K1") (pin "2") (pinfunction "2_2") (pintype "passive"))
      (node (ref "K2") (pin "2") (pinfunction "2_2") (pintype "passive"))
      (node (ref "T1") (pin "3") (pinfunction "D_3") (pintype "passive"))
    )
    (net (code "44") (name "Net-(T2-D)") (class "Default")
      (node (ref "K3") (pin "2") (pinfunction "2_2") (pintype "passive"))
      (node (ref "K4") (pin "2") (pinfunction "2_2") (pintype "passive"))
      (node (ref "T2") (pin "3") (pinfunction "D_3") (pintype "passive"))
    )
    (net (code "45") (name "Net-(U$2-C1+)") (class "Default")
      (node (ref "C5") (pin "2") (pinfunction "2_2") (pintype "passive"))
      (node (ref "U$2") (pin "9") (pinfunction "C1+_9") (pintype "bidirectional"))
    )
    (net (code "46") (name "Net-(U$2-C1-)") (class "Default")
      (node (ref "C5") (pin "1") (pinfunction "1_1") (pintype "passive"))
      (node (ref "U$2") (pin "10") (pinfunction "C1-_10") (pintype "bidirectional"))
    )
    (net (code "47") (name "Net-(U$2-VOUT)") (class "Default")
      (node (ref "C6") (pin "2") (pinfunction "2_2") (pintype "passive"))
      (node (ref "U$2") (pin "8") (pinfunction "VOUT_8") (pintype "bidirectional"))
    )
    (net (code "48") (name "Net-(U$4-VCAP)") (class "Default")
      (node (ref "C22") (pin "1") (pinfunction "1_1") (pintype "passive"))
      (node (ref "U$4") (pin "20") (pinfunction "VCAP_20") (pintype "bidirectional"))
    )
    (net (code "49") (name "Net-(U$7-A)") (class "Default")
      (node (ref "R6") (pin "1") (pinfunction "1_1") (pintype "passive"))
      (node (ref "U$7") (pin "6") (pinfunction "A_6") (pintype "bidirectional"))
      (node (ref "X5") (pin "2") (pinfunction "S_2") (pintype "passive"))
    )
    (net (code "50") (name "Net-(U$7-B)") (class "Default")
      (node (ref "R6") (pin "2") (pinfunction "2_2") (pintype "passive"))
      (node (ref "U$7") (pin "7") (pinfunction "B_7") (pintype "bidirectional"))
      (node (ref "X5") (pin "1") (pinfunction "S_1") (pintype "passive"))
    )
    (net (code "51") (name "unconnected-(U$3-IN9-Pad9)") (class "Default")
      (node (ref "U$3") (pin "9") (pinfunction "IN9_9") (pintype "bidirectional"))
    )
    (net (code "52") (name "unconnected-(U$3-IN10-Pad10)") (class "Default")
      (node (ref "U$3") (pin "10") (pinfunction "IN10_10") (pintype "bidirectional"))
    )
    (net (code "53") (name "unconnected-(U$3-IN11-Pad11)") (class "Default")
      (node (ref "U$3") (pin "11") (pinfunction "IN11_11") (pintype "bidirectional"))
    )
    (net (code "54") (name "unconnected-(U$3-IN12-Pad12)") (class "Default")
      (node (ref "U$3") (pin "12") (pinfunction "IN12_12") (pintype "bidirectional"))
    )
    (net (code "55") (name "unconnected-(U$3-IN13-Pad13)") (class "Default")
      (node (ref "U$3") (pin "13") (pinfunction "IN13_13") (pintype "bidirectional"))
    )
    (net (code "56") (name "unconnected-(U$3-IN14-Pad14)") (class "Default")
      (node (ref "U$3") (pin "14") (pinfunction "IN14_14") (pintype "bidirectional"))
    )
  )
)
